# cw506_advbreak.net
KiCad netlist of a schematic drawn in EAGLE
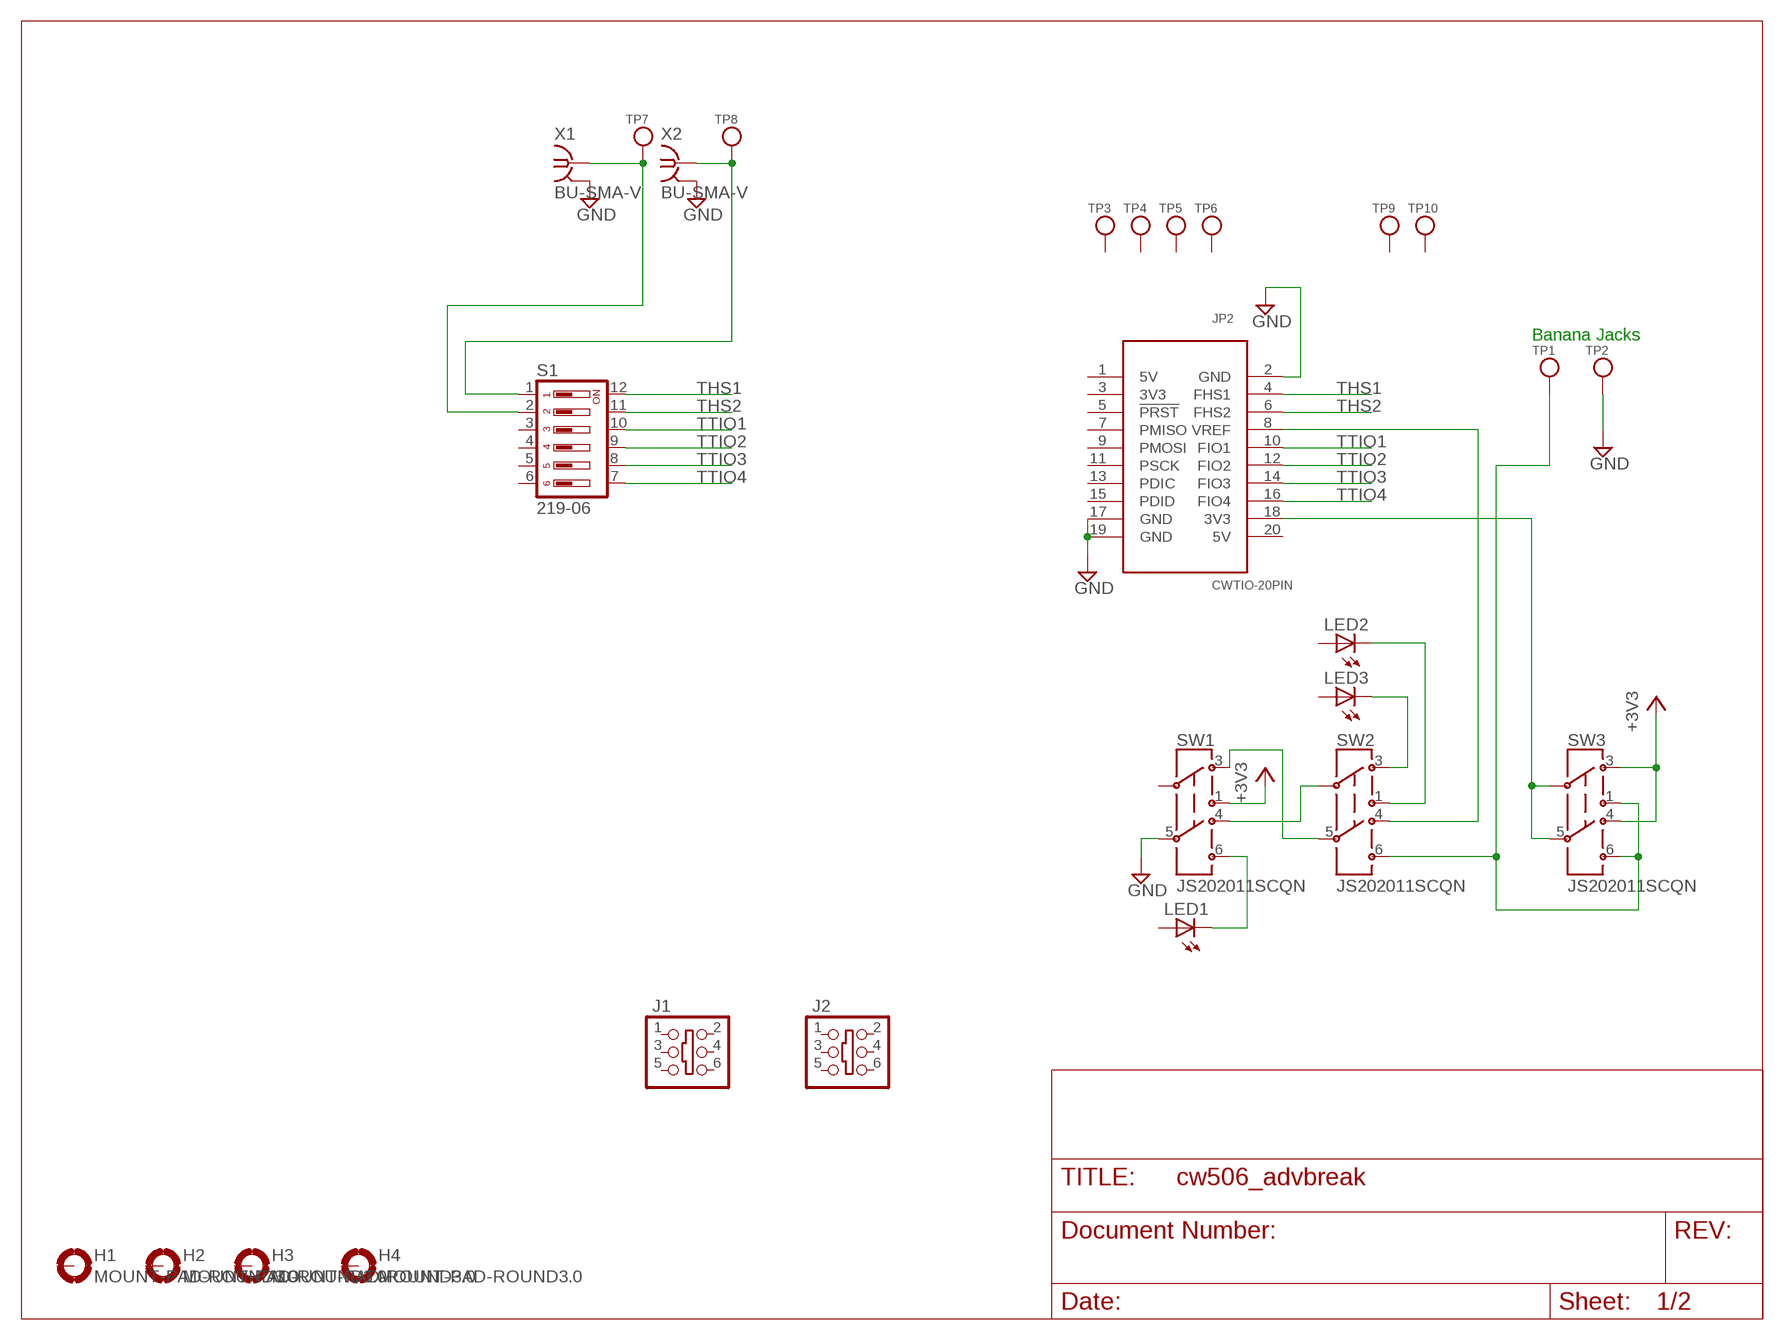
[diagram p0: schematic, sheet 1]
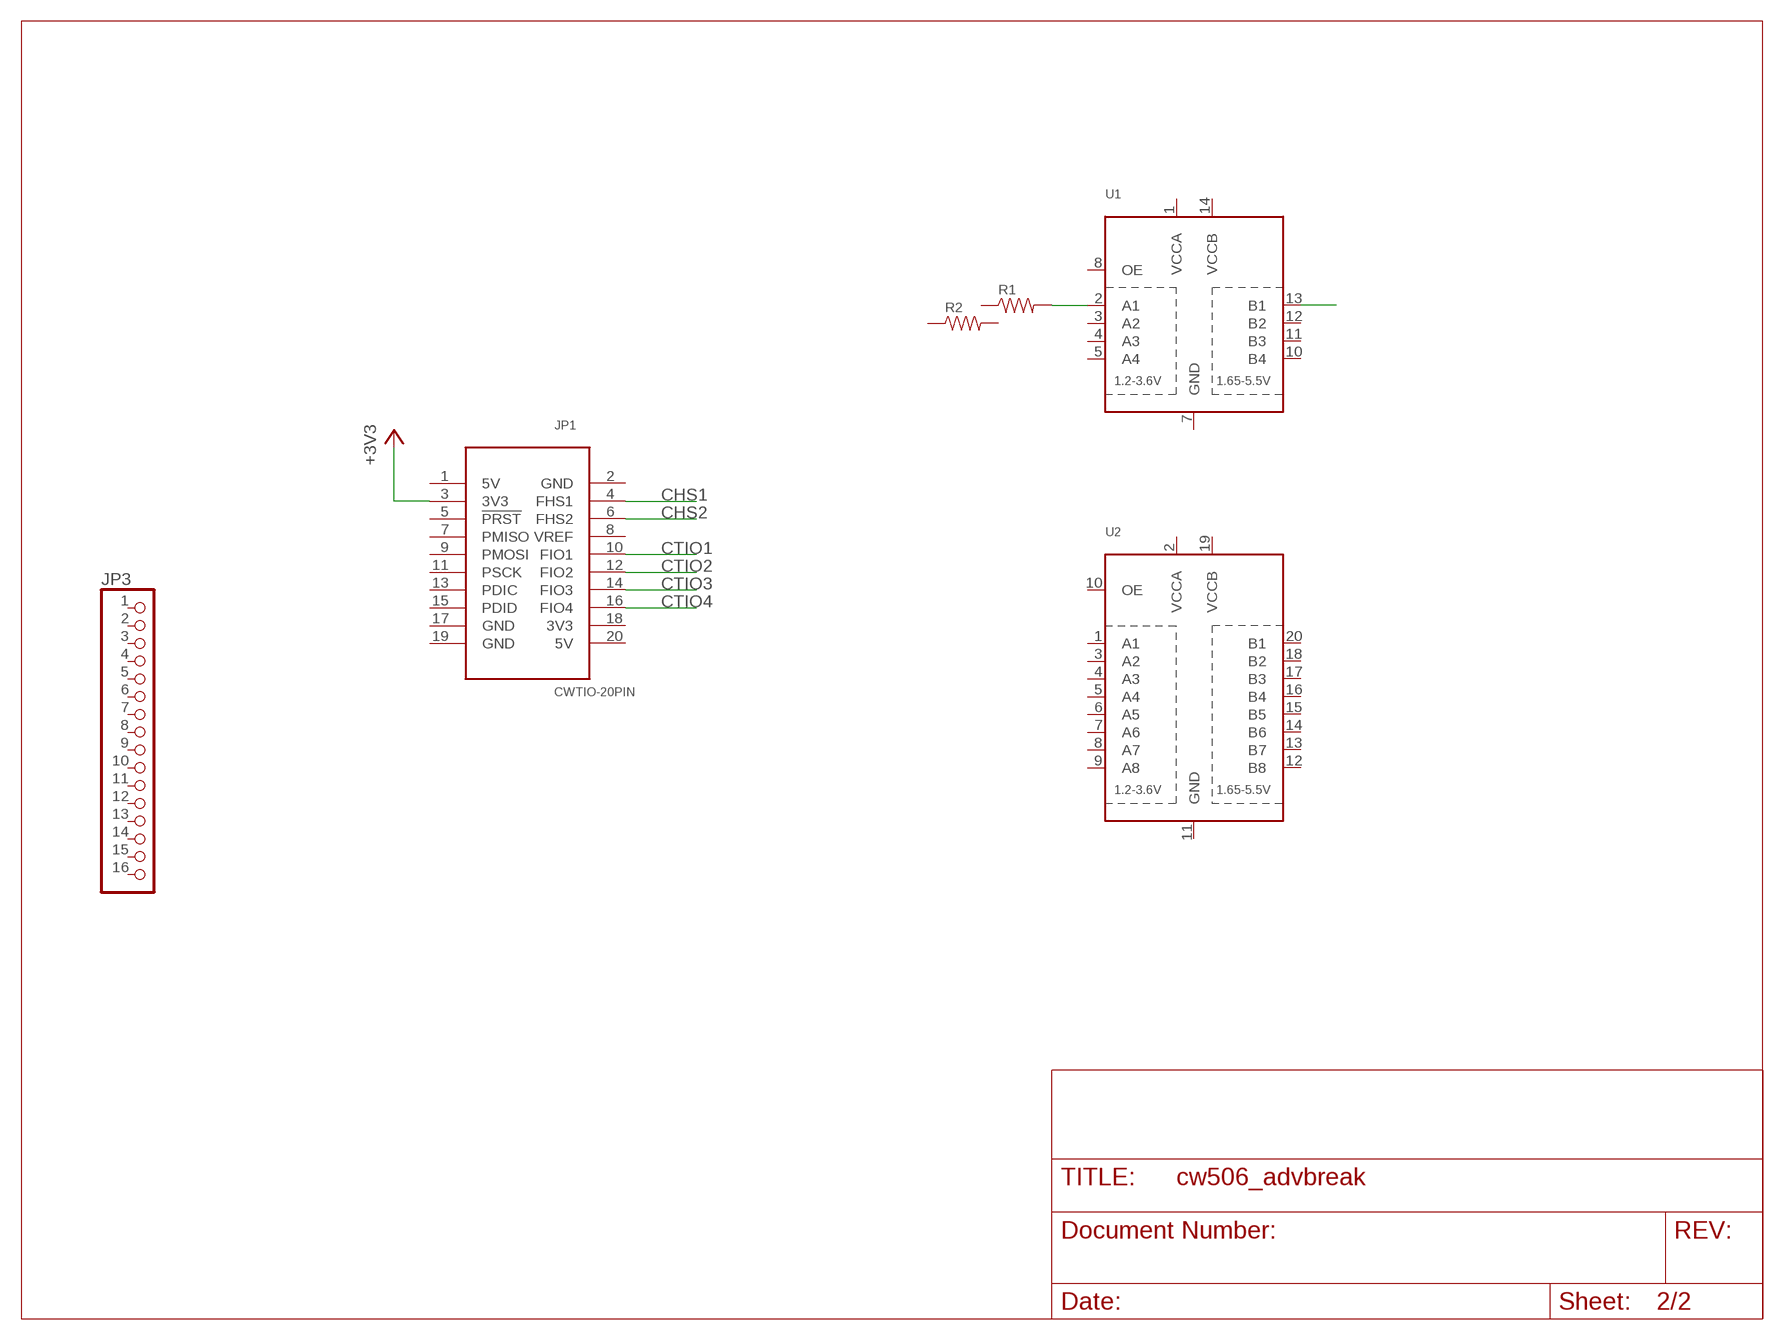
[diagram p1: schematic, sheet 2]

(export (version "E")
  (design (tool "Eeschema 10.0.6"))
  (components
    (comp (ref "JP1")
      (value "CWTIO-20PIN")
      (footprint "eagle-import:PINSHRD_PTH_2X10")
      (libsource (lib "eagle-import") (part "CWTIO-20PIN"))
    )
    (comp (ref "JP3")
      (value "PINHD-1X16")
      (footprint "eagle-import:1X16")
      (libsource (lib "eagle-import") (part "PINHD-1X16"))
    )
    (comp (ref "R1")
      (value "RES0603-RES")
      (footprint "eagle-import:0603R")
      (libsource (lib "eagle-import") (part "RES0603-RES"))
    )
    (comp (ref "R2")
      (value "RES0603-RES")
      (footprint "eagle-import:0603R")
      (libsource (lib "eagle-import") (part "RES0603-RES"))
    )
    (comp (ref "U1")
      (value "TXB0104PWR")
      (footprint "eagle-import:TSSOP14")
      (libsource (lib "eagle-import") (part "TXB0104PWR"))
    )
    (comp (ref "U2")
      (value "TXB0108PWR")
      (footprint "eagle-import:TSSOP20")
      (libsource (lib "eagle-import") (part "TXB0108PWR"))
    )
    (comp (ref "H1")
      (value "MOUNT-PAD-ROUND3.0")
      (footprint "eagle-import:3,0-PAD")
      (libsource (lib "eagle-import") (part "MOUNT-PAD-ROUND3.0"))
    )
    (comp (ref "H2")
      (value "MOUNT-PAD-ROUND3.0")
      (footprint "eagle-import:3,0-PAD")
      (libsource (lib "eagle-import") (part "MOUNT-PAD-ROUND3.0"))
    )
    (comp (ref "H3")
      (value "MOUNT-PAD-ROUND3.0")
      (footprint "eagle-import:3,0-PAD")
      (libsource (lib "eagle-import") (part "MOUNT-PAD-ROUND3.0"))
    )
    (comp (ref "H4")
      (value "MOUNT-PAD-ROUND3.0")
      (footprint "eagle-import:3,0-PAD")
      (libsource (lib "eagle-import") (part "MOUNT-PAD-ROUND3.0"))
    )
    (comp (ref "J1")
      (value "SHROUD_2X3")
      (footprint "eagle-import:PINSHRD_PTH_2X03")
      (libsource (lib "eagle-import") (part "SHROUD_2X3"))
    )
    (comp (ref "J2")
      (value "SHROUD_2X3")
      (footprint "eagle-import:PINSHRD_PTH_2X03")
      (libsource (lib "eagle-import") (part "SHROUD_2X3"))
    )
    (comp (ref "JP2")
      (value "CWTIO-20PIN")
      (footprint "eagle-import:PINSHRD_PTH_2X10")
      (libsource (lib "eagle-import") (part "CWTIO-20PIN"))
    )
    (comp (ref "LED1")
      (value "LEDCHIP-LED0603")
      (footprint "eagle-import:CHIP-LED0603")
      (libsource (lib "eagle-import") (part "LEDCHIP-LED0603"))
    )
    (comp (ref "LED2")
      (value "LEDCHIP-LED0603")
      (footprint "eagle-import:CHIP-LED0603")
      (libsource (lib "eagle-import") (part "LEDCHIP-LED0603"))
    )
    (comp (ref "LED3")
      (value "LEDCHIP-LED0603")
      (footprint "eagle-import:CHIP-LED0603")
      (libsource (lib "eagle-import") (part "LEDCHIP-LED0603"))
    )
    (comp (ref "S1")
      (value "219-06")
      (footprint "eagle-import:CTS-219-06")
      (libsource (lib "eagle-import") (part "219-06"))
    )
    (comp (ref "SW1")
      (value "JS202011SCQN")
      (footprint "eagle-import:JS202011SCQN")
      (libsource (lib "eagle-import") (part "JS202011SCQN"))
    )
    (comp (ref "SW2")
      (value "JS202011SCQN")
      (footprint "eagle-import:JS202011SCQN")
      (libsource (lib "eagle-import") (part "JS202011SCQN"))
    )
    (comp (ref "SW3")
      (value "JS202011SCQN")
      (footprint "eagle-import:JS202011SCQN")
      (libsource (lib "eagle-import") (part "JS202011SCQN"))
    )
    (comp (ref "TP1")
      (value "TPK575-4")
      (footprint "eagle-import:KEYSTONE575-4")
      (libsource (lib "eagle-import") (part "TPK575-4"))
    )
    (comp (ref "TP2")
      (value "TPK575-4")
      (footprint "eagle-import:KEYSTONE575-4")
      (libsource (lib "eagle-import") (part "TPK575-4"))
    )
    (comp (ref "TP3")
      (value "TPKEYSTONE_COMPACT")
      (footprint "eagle-import:KEYSTONE_TPCOMPACT")
      (libsource (lib "eagle-import") (part "TPKEYSTONE_COMPACT"))
    )
    (comp (ref "TP4")
      (value "TPKEYSTONE_COMPACT")
      (footprint "eagle-import:KEYSTONE_TPCOMPACT")
      (libsource (lib "eagle-import") (part "TPKEYSTONE_COMPACT"))
    )
    (comp (ref "TP5")
      (value "TPKEYSTONE_COMPACT")
      (footprint "eagle-import:KEYSTONE_TPCOMPACT")
      (libsource (lib "eagle-import") (part "TPKEYSTONE_COMPACT"))
    )
    (comp (ref "TP6")
      (value "TPKEYSTONE_COMPACT")
      (footprint "eagle-import:KEYSTONE_TPCOMPACT")
      (libsource (lib "eagle-import") (part "TPKEYSTONE_COMPACT"))
    )
    (comp (ref "TP7")
      (value "TPKEYSTONE_COMPACT")
      (footprint "eagle-import:KEYSTONE_TPCOMPACT")
      (libsource (lib "eagle-import") (part "TPKEYSTONE_COMPACT"))
    )
    (comp (ref "TP8")
      (value "TPKEYSTONE_COMPACT")
      (footprint "eagle-import:KEYSTONE_TPCOMPACT")
      (libsource (lib "eagle-import") (part "TPKEYSTONE_COMPACT"))
    )
    (comp (ref "TP9")
      (value "TPKEYSTONE_COMPACT")
      (footprint "eagle-import:KEYSTONE_TPCOMPACT")
      (libsource (lib "eagle-import") (part "TPKEYSTONE_COMPACT"))
    )
    (comp (ref "TP10")
      (value "TPKEYSTONE_COMPACT")
      (footprint "eagle-import:KEYSTONE_TPCOMPACT")
      (libsource (lib "eagle-import") (part "TPKEYSTONE_COMPACT"))
    )
    (comp (ref "X1")
      (value "BU-SMA-V")
      (footprint "eagle-import:BU-SMA-V")
      (libsource (lib "eagle-import") (part "BU-SMA-V"))
    )
    (comp (ref "X2")
      (value "BU-SMA-V")
      (footprint "eagle-import:BU-SMA-V")
      (libsource (lib "eagle-import") (part "BU-SMA-V"))
    )
  )
  (nets
    (net (code "1") (name "+3V3") (class "Default")
      (node (ref "JP1") (pin "3") (pinfunction "3V3_3") (pintype "bidirectional"))
      (node (ref "SW1") (pin "1") (pinfunction "3_1") (pintype "bidirectional"))
      (node (ref "SW3") (pin "3") (pinfunction "1_3") (pintype "bidirectional"))
      (node (ref "SW3") (pin "4") (pinfunction "6_4") (pintype "bidirectional"))
    )
    (net (code "2") (name "CHS1") (class "Default")
      (node (ref "JP1") (pin "4") (pinfunction "FHS1_4") (pintype "bidirectional"))
    )
    (net (code "3") (name "CHS2") (class "Default")
      (node (ref "JP1") (pin "6") (pinfunction "FHS2_6") (pintype "bidirectional"))
    )
    (net (code "4") (name "CTIO1") (class "Default")
      (node (ref "JP1") (pin "10") (pinfunction "FIO1_10") (pintype "bidirectional"))
    )
    (net (code "5") (name "CTIO2") (class "Default")
      (node (ref "JP1") (pin "12") (pinfunction "FIO2_12") (pintype "bidirectional"))
    )
    (net (code "6") (name "CTIO3") (class "Default")
      (node (ref "JP1") (pin "14") (pinfunction "FIO3_14") (pintype "bidirectional"))
    )
    (net (code "7") (name "CTIO4") (class "Default")
      (node (ref "JP1") (pin "16") (pinfunction "FIO4_16") (pintype "bidirectional"))
    )
    (net (code "8") (name "GND") (class "Default")
      (node (ref "JP2") (pin "17") (pinfunction "GND_17") (pintype "bidirectional"))
      (node (ref "JP2") (pin "19") (pinfunction "GND_19") (pintype "bidirectional"))
      (node (ref "JP2") (pin "2") (pinfunction "GND_2") (pintype "bidirectional"))
      (node (ref "SW1") (pin "5") (pinfunction "5_5") (pintype "bidirectional"))
      (node (ref "TP2") (pin "1") (pinfunction "TP_1") (pintype "bidirectional"))
      (node (ref "X1") (pin "2") (pinfunction "2_2") (pintype "passive"))
      (node (ref "X1") (pin "3") (pinfunction "2_3") (pintype "passive"))
      (node (ref "X1") (pin "4") (pinfunction "2_4") (pintype "passive"))
      (node (ref "X1") (pin "5") (pinfunction "2_5") (pintype "passive"))
      (node (ref "X2") (pin "2") (pinfunction "2_2") (pintype "passive"))
      (node (ref "X2") (pin "3") (pinfunction "2_3") (pintype "passive"))
      (node (ref "X2") (pin "4") (pinfunction "2_4") (pintype "passive"))
      (node (ref "X2") (pin "5") (pinfunction "2_5") (pintype "passive"))
    )
    (net (code "9") (name "Net-(JP2-3V3-Pad18)") (class "Default")
      (node (ref "JP2") (pin "18") (pinfunction "3V3_18") (pintype "bidirectional"))
      (node (ref "SW3") (pin "2") (pinfunction "2_2") (pintype "bidirectional"))
      (node (ref "SW3") (pin "5") (pinfunction "5_5") (pintype "bidirectional"))
    )
    (net (code "10") (name "Net-(JP2-VREF)") (class "Default")
      (node (ref "JP2") (pin "8") (pinfunction "VREF_8") (pintype "bidirectional"))
      (node (ref "SW2") (pin "4") (pinfunction "6_4") (pintype "bidirectional"))
    )
    (net (code "11") (name "Net-(SW1-1)") (class "Default")
      (node (ref "SW1") (pin "3") (pinfunction "1_3") (pintype "bidirectional"))
      (node (ref "SW2") (pin "5") (pinfunction "5_5") (pintype "bidirectional"))
    )
    (net (code "12") (name "Net-(SW1-4)") (class "Default")
      (node (ref "LED1") (pin "C") (pinfunction "C_C") (pintype "passive"))
      (node (ref "SW1") (pin "6") (pinfunction "4_6") (pintype "bidirectional"))
    )
    (net (code "13") (name "Net-(SW1-6)") (class "Default")
      (node (ref "SW1") (pin "4") (pinfunction "6_4") (pintype "bidirectional"))
      (node (ref "SW2") (pin "2") (pinfunction "2_2") (pintype "bidirectional"))
    )
    (net (code "14") (name "Net-(SW2-1)") (class "Default")
      (node (ref "LED3") (pin "C") (pinfunction "C_C") (pintype "passive"))
      (node (ref "SW2") (pin "3") (pinfunction "1_3") (pintype "bidirectional"))
    )
    (net (code "15") (name "Net-(SW2-3)") (class "Default")
      (node (ref "LED2") (pin "C") (pinfunction "C_C") (pintype "passive"))
      (node (ref "SW2") (pin "1") (pinfunction "3_1") (pintype "bidirectional"))
    )
    (net (code "16") (name "Net-(SW2-4)") (class "Default")
      (node (ref "SW2") (pin "6") (pinfunction "4_6") (pintype "bidirectional"))
      (node (ref "SW3") (pin "1") (pinfunction "3_1") (pintype "bidirectional"))
      (node (ref "SW3") (pin "6") (pinfunction "4_6") (pintype "bidirectional"))
      (node (ref "TP1") (pin "1") (pinfunction "TP_1") (pintype "bidirectional"))
    )
    (net (code "17") (name "Net-(TP7-TP)") (class "Default")
      (node (ref "S1") (pin "2") (pinfunction "2_2") (pintype "passive"))
      (node (ref "TP7") (pin "1") (pinfunction "TP_1") (pintype "bidirectional"))
      (node (ref "X1") (pin "1") (pinfunction "1_1") (pintype "passive"))
    )
    (net (code "18") (name "Net-(TP8-TP)") (class "Default")
      (node (ref "S1") (pin "1") (pinfunction "1_1") (pintype "passive"))
      (node (ref "TP8") (pin "1") (pinfunction "TP_1") (pintype "bidirectional"))
      (node (ref "X2") (pin "1") (pinfunction "1_1") (pintype "passive"))
    )
    (net (code "19") (name "Net-(U1-A1)") (class "Default")
      (node (ref "R1") (pin "2") (pinfunction "2_2") (pintype "passive"))
      (node (ref "U1") (pin "2") (pinfunction "A1_2") (pintype "bidirectional"))
    )
    (net (code "20") (name "THS1") (class "Default")
      (node (ref "JP2") (pin "4") (pinfunction "FHS1_4") (pintype "bidirectional"))
      (node (ref "S1") (pin "12") (pinfunction "12_12") (pintype "passive"))
    )
    (net (code "21") (name "THS2") (class "Default")
      (node (ref "JP2") (pin "6") (pinfunction "FHS2_6") (pintype "bidirectional"))
      (node (ref "S1") (pin "11") (pinfunction "11_11") (pintype "passive"))
    )
    (net (code "22") (name "TTIO1") (class "Default")
      (node (ref "JP2") (pin "10") (pinfunction "FIO1_10") (pintype "bidirectional"))
      (node (ref "S1") (pin "10") (pinfunction "10_10") (pintype "passive"))
    )
    (net (code "23") (name "TTIO2") (class "Default")
      (node (ref "JP2") (pin "12") (pinfunction "FIO2_12") (pintype "bidirectional"))
      (node (ref "S1") (pin "9") (pinfunction "9_9") (pintype "passive"))
    )
    (net (code "24") (name "TTIO3") (class "Default")
      (node (ref "JP2") (pin "14") (pinfunction "FIO3_14") (pintype "bidirectional"))
      (node (ref "S1") (pin "8") (pinfunction "8_8") (pintype "passive"))
    )
    (net (code "25") (name "TTIO4") (class "Default")
      (node (ref "JP2") (pin "16") (pinfunction "FIO4_16") (pintype "bidirectional"))
      (node (ref "S1") (pin "7") (pinfunction "7_7") (pintype "passive"))
    )
    (net (code "26") (name "unconnected-(H1-MOUNT-PadB3,0)") (class "Default")
      (node (ref "H1") (pin "B3,0") (pinfunction "MOUNT_B3,0") (pintype "passive"))
    )
    (net (code "27") (name "unconnected-(H2-MOUNT-PadB3,0)") (class "Default")
      (node (ref "H2") (pin "B3,0") (pinfunction "MOUNT_B3,0") (pintype "passive"))
    )
    (net (code "28") (name "unconnected-(H3-MOUNT-PadB3,0)") (class "Default")
      (node (ref "H3") (pin "B3,0") (pinfunction "MOUNT_B3,0") (pintype "passive"))
    )
    (net (code "29") (name "unconnected-(H4-MOUNT-PadB3,0)") (class "Default")
      (node (ref "H4") (pin "B3,0") (pinfunction "MOUNT_B3,0") (pintype "passive"))
    )
    (net (code "30") (name "unconnected-(J1-Pad1)") (class "Default")
      (node (ref "J1") (pin "1") (pinfunction "1_1") (pintype "passive"))
    )
    (net (code "31") (name "unconnected-(J1-Pad2)") (class "Default")
      (node (ref "J1") (pin "2") (pinfunction "2_2") (pintype "passive"))
    )
    (net (code "32") (name "unconnected-(J1-Pad3)") (class "Default")
      (node (ref "J1") (pin "3") (pinfunction "3_3") (pintype "passive"))
    )
    (net (code "33") (name "unconnected-(J1-Pad4)") (class "Default")
      (node (ref "J1") (pin "4") (pinfunction "4_4") (pintype "passive"))
    )
    (net (code "34") (name "unconnected-(J1-Pad5)") (class "Default")
      (node (ref "J1") (pin "5") (pinfunction "5_5") (pintype "passive"))
    )
    (net (code "35") (name "unconnected-(J1-Pad6)") (class "Default")
      (node (ref "J1") (pin "6") (pinfunction "6_6") (pintype "passive"))
    )
    (net (code "36") (name "unconnected-(J2-Pad1)") (class "Default")
      (node (ref "J2") (pin "1") (pinfunction "1_1") (pintype "passive"))
    )
    (net (code "37") (name "unconnected-(J2-Pad2)") (class "Default")
      (node (ref "J2") (pin "2") (pinfunction "2_2") (pintype "passive"))
    )
    (net (code "38") (name "unconnected-(J2-Pad3)") (class "Default")
      (node (ref "J2") (pin "3") (pinfunction "3_3") (pintype "passive"))
    )
    (net (code "39") (name "unconnected-(J2-Pad4)") (class "Default")
      (node (ref "J2") (pin "4") (pinfunction "4_4") (pintype "passive"))
    )
    (net (code "40") (name "unconnected-(J2-Pad5)") (class "Default")
      (node (ref "J2") (pin "5") (pinfunction "5_5") (pintype "passive"))
    )
    (net (code "41") (name "unconnected-(J2-Pad6)") (class "Default")
      (node (ref "J2") (pin "6") (pinfunction "6_6") (pintype "passive"))
    )
    (net (code "42") (name "unconnected-(JP1-3V3-Pad18)") (class "Default")
      (node (ref "JP1") (pin "18") (pinfunction "3V3_18") (pintype "bidirectional"))
    )
    (net (code "43") (name "unconnected-(JP1-5V-Pad1)") (class "Default")
      (node (ref "JP1") (pin "1") (pinfunction "5V_1") (pintype "bidirectional"))
    )
    (net (code "44") (name "unconnected-(JP1-5V-Pad20)") (class "Default")
      (node (ref "JP1") (pin "20") (pinfunction "5V_20") (pintype "bidirectional"))
    )
    (net (code "45") (name "unconnected-(JP1-GND-Pad2)") (class "Default")
      (node (ref "JP1") (pin "2") (pinfunction "GND_2") (pintype "bidirectional"))
    )
    (net (code "46") (name "unconnected-(JP1-GND-Pad17)") (class "Default")
      (node (ref "JP1") (pin "17") (pinfunction "GND_17") (pintype "bidirectional"))
    )
    (net (code "47") (name "unconnected-(JP1-GND-Pad19)") (class "Default")
      (node (ref "JP1") (pin "19") (pinfunction "GND_19") (pintype "bidirectional"))
    )
    (net (code "48") (name "unconnected-(JP1-PDIC-Pad13)") (class "Default")
      (node (ref "JP1") (pin "13") (pinfunction "PDIC_13") (pintype "bidirectional"))
    )
    (net (code "49") (name "unconnected-(JP1-PDID-Pad15)") (class "Default")
      (node (ref "JP1") (pin "15") (pinfunction "PDID_15") (pintype "bidirectional"))
    )
    (net (code "50") (name "unconnected-(JP1-PMISO-Pad7)") (class "Default")
      (node (ref "JP1") (pin "7") (pinfunction "PMISO_7") (pintype "bidirectional"))
    )
    (net (code "51") (name "unconnected-(JP1-PMOSI-Pad9)") (class "Default")
      (node (ref "JP1") (pin "9") (pinfunction "PMOSI_9") (pintype "bidirectional"))
    )
    (net (code "52") (name "unconnected-(JP1-PSCK-Pad11)") (class "Default")
      (node (ref "JP1") (pin "11") (pinfunction "PSCK_11") (pintype "bidirectional"))
    )
    (net (code "53") (name "unconnected-(JP1-VREF-Pad8)") (class "Default")
      (node (ref "JP1") (pin "8") (pinfunction "VREF_8") (pintype "bidirectional"))
    )
    (net (code "54") (name "unconnected-(JP1-~{PRST}-Pad5)") (class "Default")
      (node (ref "JP1") (pin "5") (pinfunction "~{PRST}_5") (pintype "bidirectional"))
    )
    (net (code "55") (name "unconnected-(JP2-3V3-Pad3)") (class "Default")
      (node (ref "JP2") (pin "3") (pinfunction "3V3_3") (pintype "bidirectional"))
    )
    (net (code "56") (name "unconnected-(JP2-5V-Pad1)") (class "Default")
      (node (ref "JP2") (pin "1") (pinfunction "5V_1") (pintype "bidirectional"))
    )
    (net (code "57") (name "unconnected-(JP2-5V-Pad20)") (class "Default")
      (node (ref "JP2") (pin "20") (pinfunction "5V_20") (pintype "bidirectional"))
    )
    (net (code "58") (name "unconnected-(JP2-PDIC-Pad13)") (class "Default")
      (node (ref "JP2") (pin "13") (pinfunction "PDIC_13") (pintype "bidirectional"))
    )
    (net (code "59") (name "unconnected-(JP2-PDID-Pad15)") (class "Default")
      (node (ref "JP2") (pin "15") (pinfunction "PDID_15") (pintype "bidirectional"))
    )
    (net (code "60") (name "unconnected-(JP2-PMISO-Pad7)") (class "Default")
      (node (ref "JP2") (pin "7") (pinfunction "PMISO_7") (pintype "bidirectional"))
    )
    (net (code "61") (name "unconnected-(JP2-PMOSI-Pad9)") (class "Default")
      (node (ref "JP2") (pin "9") (pinfunction "PMOSI_9") (pintype "bidirectional"))
    )
    (net (code "62") (name "unconnected-(JP2-PSCK-Pad11)") (class "Default")
      (node (ref "JP2") (pin "11") (pinfunction "PSCK_11") (pintype "bidirectional"))
    )
    (net (code "63") (name "unconnected-(JP2-~{PRST}-Pad5)") (class "Default")
      (node (ref "JP2") (pin "5") (pinfunction "~{PRST}_5") (pintype "bidirectional"))
    )
    (net (code "64") (name "unconnected-(JP3-Pad1)") (class "Default")
      (node (ref "JP3") (pin "1") (pinfunction "1_1") (pintype "passive"))
    )
    (net (code "65") (name "unconnected-(JP3-Pad2)") (class "Default")
      (node (ref "JP3") (pin "2") (pinfunction "2_2") (pintype "passive"))
    )
    (net (code "66") (name "unconnected-(JP3-Pad3)") (class "Default")
      (node (ref "JP3") (pin "3") (pinfunction "3_3") (pintype "passive"))
    )
    (net (code "67") (name "unconnected-(JP3-Pad4)") (class "Default")
      (node (ref "JP3") (pin "4") (pinfunction "4_4") (pintype "passive"))
    )
    (net (code "68") (name "unconnected-(JP3-Pad5)") (class "Default")
      (node (ref "JP3") (pin "5") (pinfunction "5_5") (pintype "passive"))
    )
    (net (code "69") (name "unconnected-(JP3-Pad6)") (class "Default")
      (node (ref "JP3") (pin "6") (pinfunction "6_6") (pintype "passive"))
    )
    (net (code "70") (name "unconnected-(JP3-Pad7)") (class "Default")
      (node (ref "JP3") (pin "7") (pinfunction "7_7") (pintype "passive"))
    )
    (net (code "71") (name "unconnected-(JP3-Pad8)") (class "Default")
      (node (ref "JP3") (pin "8") (pinfunction "8_8") (pintype "passive"))
    )
    (net (code "72") (name "unconnected-(JP3-Pad9)") (class "Default")
      (node (ref "JP3") (pin "9") (pinfunction "9_9") (pintype "passive"))
    )
    (net (code "73") (name "unconnected-(JP3-Pad10)") (class "Default")
      (node (ref "JP3") (pin "10") (pinfunction "10_10") (pintype "passive"))
    )
    (net (code "74") (name "unconnected-(JP3-Pad11)") (class "Default")
      (node (ref "JP3") (pin "11") (pinfunction "11_11") (pintype "passive"))
    )
    (net (code "75") (name "unconnected-(JP3-Pad12)") (class "Default")
      (node (ref "JP3") (pin "12") (pinfunction "12_12") (pintype "passive"))
    )
    (net (code "76") (name "unconnected-(JP3-Pad13)") (class "Default")
      (node (ref "JP3") (pin "13") (pinfunction "13_13") (pintype "passive"))
    )
    (net (code "77") (name "unconnected-(JP3-Pad14)") (class "Default")
      (node (ref "JP3") (pin "14") (pinfunction "14_14") (pintype "passive"))
    )
    (net (code "78") (name "unconnected-(JP3-Pad15)") (class "Default")
      (node (ref "JP3") (pin "15") (pinfunction "15_15") (pintype "passive"))
    )
    (net (code "79") (name "unconnected-(JP3-Pad16)") (class "Default")
      (node (ref "JP3") (pin "16") (pinfunction "16_16") (pintype "passive"))
    )
    (net (code "80") (name "unconnected-(LED1-PadA)") (class "Default")
      (node (ref "LED1") (pin "A") (pinfunction "A_A") (pintype "passive"))
    )
    (net (code "81") (name "unconnected-(LED2-PadA)") (class "Default")
      (node (ref "LED2") (pin "A") (pinfunction "A_A") (pintype "passive"))
    )
    (net (code "82") (name "unconnected-(LED3-PadA)") (class "Default")
      (node (ref "LED3") (pin "A") (pinfunction "A_A") (pintype "passive"))
    )
    (net (code "83") (name "unconnected-(R1-Pad1)") (class "Default")
      (node (ref "R1") (pin "1") (pinfunction "1_1") (pintype "passive"))
    )
    (net (code "84") (name "unconnected-(R2-Pad1)") (class "Default")
      (node (ref "R2") (pin "1") (pinfunction "1_1") (pintype "passive"))
    )
    (net (code "85") (name "unconnected-(R2-Pad2)") (class "Default")
      (node (ref "R2") (pin "2") (pinfunction "2_2") (pintype "passive"))
    )
    (net (code "86") (name "unconnected-(S1-Pad3)") (class "Default")
      (node (ref "S1") (pin "3") (pinfunction "3_3") (pintype "passive"))
    )
    (net (code "87") (name "unconnected-(S1-Pad4)") (class "Default")
      (node (ref "S1") (pin "4") (pinfunction "4_4") (pintype "passive"))
    )
    (net (code "88") (name "unconnected-(S1-Pad5)") (class "Default")
      (node (ref "S1") (pin "5") (pinfunction "5_5") (pintype "passive"))
    )
    (net (code "89") (name "unconnected-(S1-Pad6)") (class "Default")
      (node (ref "S1") (pin "6") (pinfunction "6_6") (pintype "passive"))
    )
    (net (code "90") (name "unconnected-(SW1-Pad2)") (class "Default")
      (node (ref "SW1") (pin "2") (pinfunction "2_2") (pintype "bidirectional"))
    )
    (net (code "91") (name "unconnected-(TP3-TP-Pad1)") (class "Default")
      (node (ref "TP3") (pin "1") (pinfunction "TP_1") (pintype "bidirectional"))
    )
    (net (code "92") (name "unconnected-(TP4-TP-Pad1)") (class "Default")
      (node (ref "TP4") (pin "1") (pinfunction "TP_1") (pintype "bidirectional"))
    )
    (net (code "93") (name "unconnected-(TP5-TP-Pad1)") (class "Default")
      (node (ref "TP5") (pin "1") (pinfunction "TP_1") (pintype "bidirectional"))
    )
    (net (code "94") (name "unconnected-(TP6-TP-Pad1)") (class "Default")
      (node (ref "TP6") (pin "1") (pinfunction "TP_1") (pintype "bidirectional"))
    )
    (net (code "95") (name "unconnected-(TP9-TP-Pad1)") (class "Default")
      (node (ref "TP9") (pin "1") (pinfunction "TP_1") (pintype "bidirectional"))
    )
    (net (code "96") (name "unconnected-(TP10-TP-Pad1)") (class "Default")
      (node (ref "TP10") (pin "1") (pinfunction "TP_1") (pintype "bidirectional"))
    )
    (net (code "97") (name "unconnected-(U1-A2-Pad3)") (class "Default")
      (node (ref "U1") (pin "3") (pinfunction "A2_3") (pintype "bidirectional"))
    )
    (net (code "98") (name "unconnected-(U1-A3-Pad4)") (class "Default")
      (node (ref "U1") (pin "4") (pinfunction "A3_4") (pintype "bidirectional"))
    )
    (net (code "99") (name "unconnected-(U1-A4-Pad5)") (class "Default")
      (node (ref "U1") (pin "5") (pinfunction "A4_5") (pintype "bidirectional"))
    )
    (net (code "100") (name "unconnected-(U1-B1-Pad13)") (class "Default")
      (node (ref "U1") (pin "13") (pinfunction "B1_13") (pintype "bidirectional"))
    )
    (net (code "101") (name "unconnected-(U1-B2-Pad12)") (class "Default")
      (node (ref "U1") (pin "12") (pinfunction "B2_12") (pintype "bidirectional"))
    )
    (net (code "102") (name "unconnected-(U1-B3-Pad11)") (class "Default")
      (node (ref "U1") (pin "11") (pinfunction "B3_11") (pintype "bidirectional"))
    )
    (net (code "103") (name "unconnected-(U1-B4-Pad10)") (class "Default")
      (node (ref "U1") (pin "10") (pinfunction "B4_10") (pintype "bidirectional"))
    )
    (net (code "104") (name "unconnected-(U1-GND-Pad7)") (class "Default")
      (node (ref "U1") (pin "7") (pinfunction "GND_7") (pintype "bidirectional"))
    )
    (net (code "105") (name "unconnected-(U1-OE-Pad8)") (class "Default")
      (node (ref "U1") (pin "8") (pinfunction "OE_8") (pintype "bidirectional"))
    )
    (net (code "106") (name "unconnected-(U1-VCCA-Pad1)") (class "Default")
      (node (ref "U1") (pin "1") (pinfunction "VCCA_1") (pintype "bidirectional"))
    )
    (net (code "107") (name "unconnected-(U1-VCCB-Pad14)") (class "Default")
      (node (ref "U1") (pin "14") (pinfunction "VCCB_14") (pintype "bidirectional"))
    )
    (net (code "108") (name "unconnected-(U2-A1-Pad1)") (class "Default")
      (node (ref "U2") (pin "1") (pinfunction "A1_1") (pintype "bidirectional"))
    )
    (net (code "109") (name "unconnected-(U2-A2-Pad3)") (class "Default")
      (node (ref "U2") (pin "3") (pinfunction "A2_3") (pintype "bidirectional"))
    )
    (net (code "110") (name "unconnected-(U2-A3-Pad4)") (class "Default")
      (node (ref "U2") (pin "4") (pinfunction "A3_4") (pintype "bidirectional"))
    )
    (net (code "111") (name "unconnected-(U2-A4-Pad5)") (class "Default")
      (node (ref "U2") (pin "5") (pinfunction "A4_5") (pintype "bidirectional"))
    )
    (net (code "112") (name "unconnected-(U2-A5-Pad6)") (class "Default")
      (node (ref "U2") (pin "6") (pinfunction "A5_6") (pintype "bidirectional"))
    )
    (net (code "113") (name "unconnected-(U2-A6-Pad7)") (class "Default")
      (node (ref "U2") (pin "7") (pinfunction "A6_7") (pintype "bidirectional"))
    )
    (net (code "114") (name "unconnected-(U2-A7-Pad8)") (class "Default")
      (node (ref "U2") (pin "8") (pinfunction "A7_8") (pintype "bidirectional"))
    )
    (net (code "115") (name "unconnected-(U2-A8-Pad9)") (class "Default")
      (node (ref "U2") (pin "9") (pinfunction "A8_9") (pintype "bidirectional"))
    )
    (net (code "116") (name "unconnected-(U2-B1-Pad20)") (class "Default")
      (node (ref "U2") (pin "20") (pinfunction "B1_20") (pintype "bidirectional"))
    )
    (net (code "117") (name "unconnected-(U2-B2-Pad18)") (class "Default")
      (node (ref "U2") (pin "18") (pinfunction "B2_18") (pintype "bidirectional"))
    )
    (net (code "118") (name "unconnected-(U2-B3-Pad17)") (class "Default")
      (node (ref "U2") (pin "17") (pinfunction "B3_17") (pintype "bidirectional"))
    )
    (net (code "119") (name "unconnected-(U2-B4-Pad16)") (class "Default")
      (node (ref "U2") (pin "16") (pinfunction "B4_16") (pintype "bidirectional"))
    )
    (net (code "120") (name "unconnected-(U2-B5-Pad15)") (class "Default")
      (node (ref "U2") (pin "15") (pinfunction "B5_15") (pintype "bidirectional"))
    )
    (net (code "121") (name "unconnected-(U2-B6-Pad14)") (class "Default")
      (node (ref "U2") (pin "14") (pinfunction "B6_14") (pintype "bidirectional"))
    )
    (net (code "122") (name "unconnected-(U2-B7-Pad13)") (class "Default")
      (node (ref "U2") (pin "13") (pinfunction "B7_13") (pintype "bidirectional"))
    )
    (net (code "123") (name "unconnected-(U2-B8-Pad12)") (class "Default")
      (node (ref "U2") (pin "12") (pinfunction "B8_12") (pintype "bidirectional"))
    )
    (net (code "124") (name "unconnected-(U2-GND-Pad11)") (class "Default")
      (node (ref "U2") (pin "11") (pinfunction "GND_11") (pintype "bidirectional"))
    )
    (net (code "125") (name "unconnected-(U2-OE-Pad10)") (class "Default")
      (node (ref "U2") (pin "10") (pinfunction "OE_10") (pintype "bidirectional"))
    )
    (net (code "126") (name "unconnected-(U2-VCCA-Pad2)") (class "Default")
      (node (ref "U2") (pin "2") (pinfunction "VCCA_2") (pintype "bidirectional"))
    )
    (net (code "127") (name "unconnected-(U2-VCCB-Pad19)") (class "Default")
      (node (ref "U2") (pin "19") (pinfunction "VCCB_19") (pintype "bidirectional"))
    )
  )
)
